# 16_RK3568_VI_Interface.net
KiCad netlist of a schematic drawn in Altium Designer
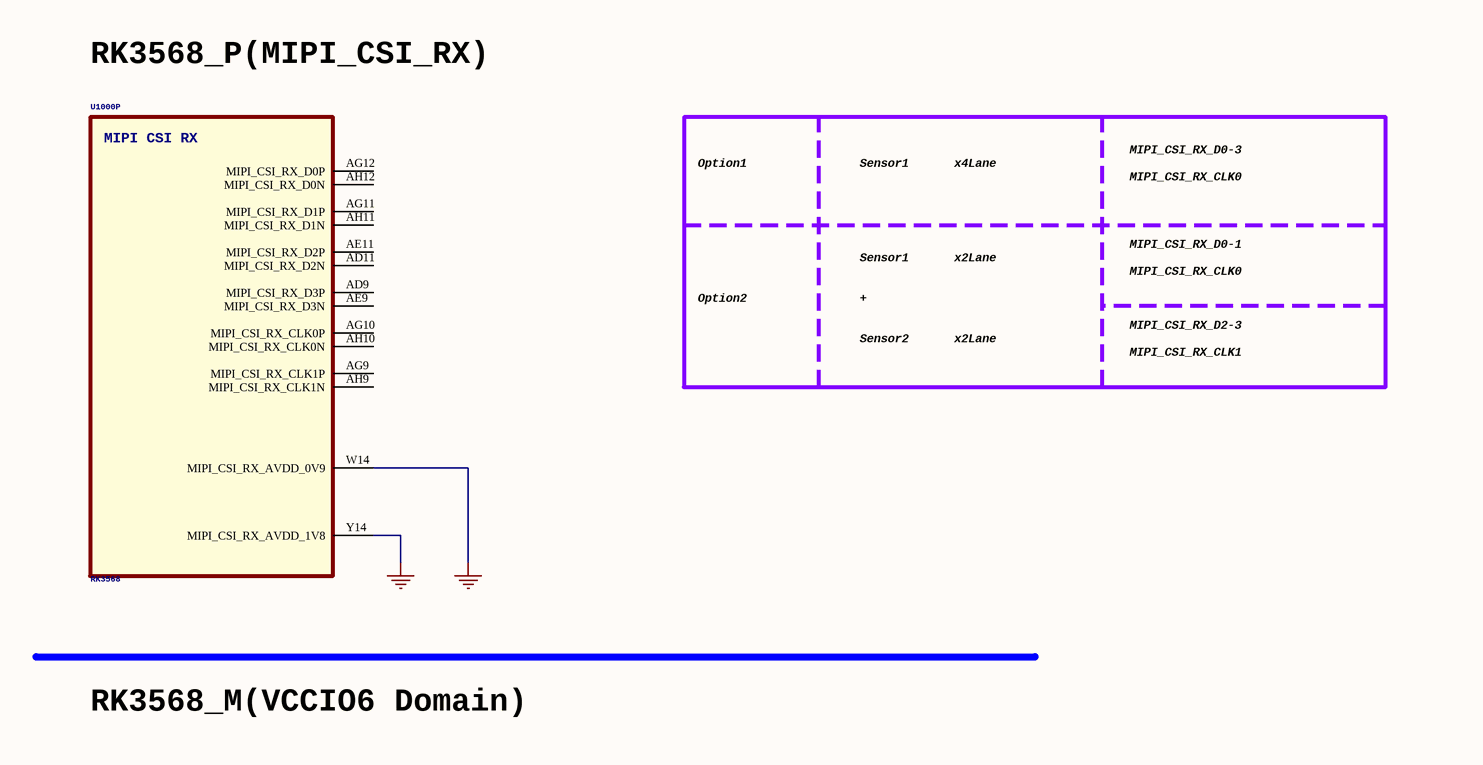
[diagram p0: 16.RK3568_VI Interface.SchDoc, top left]
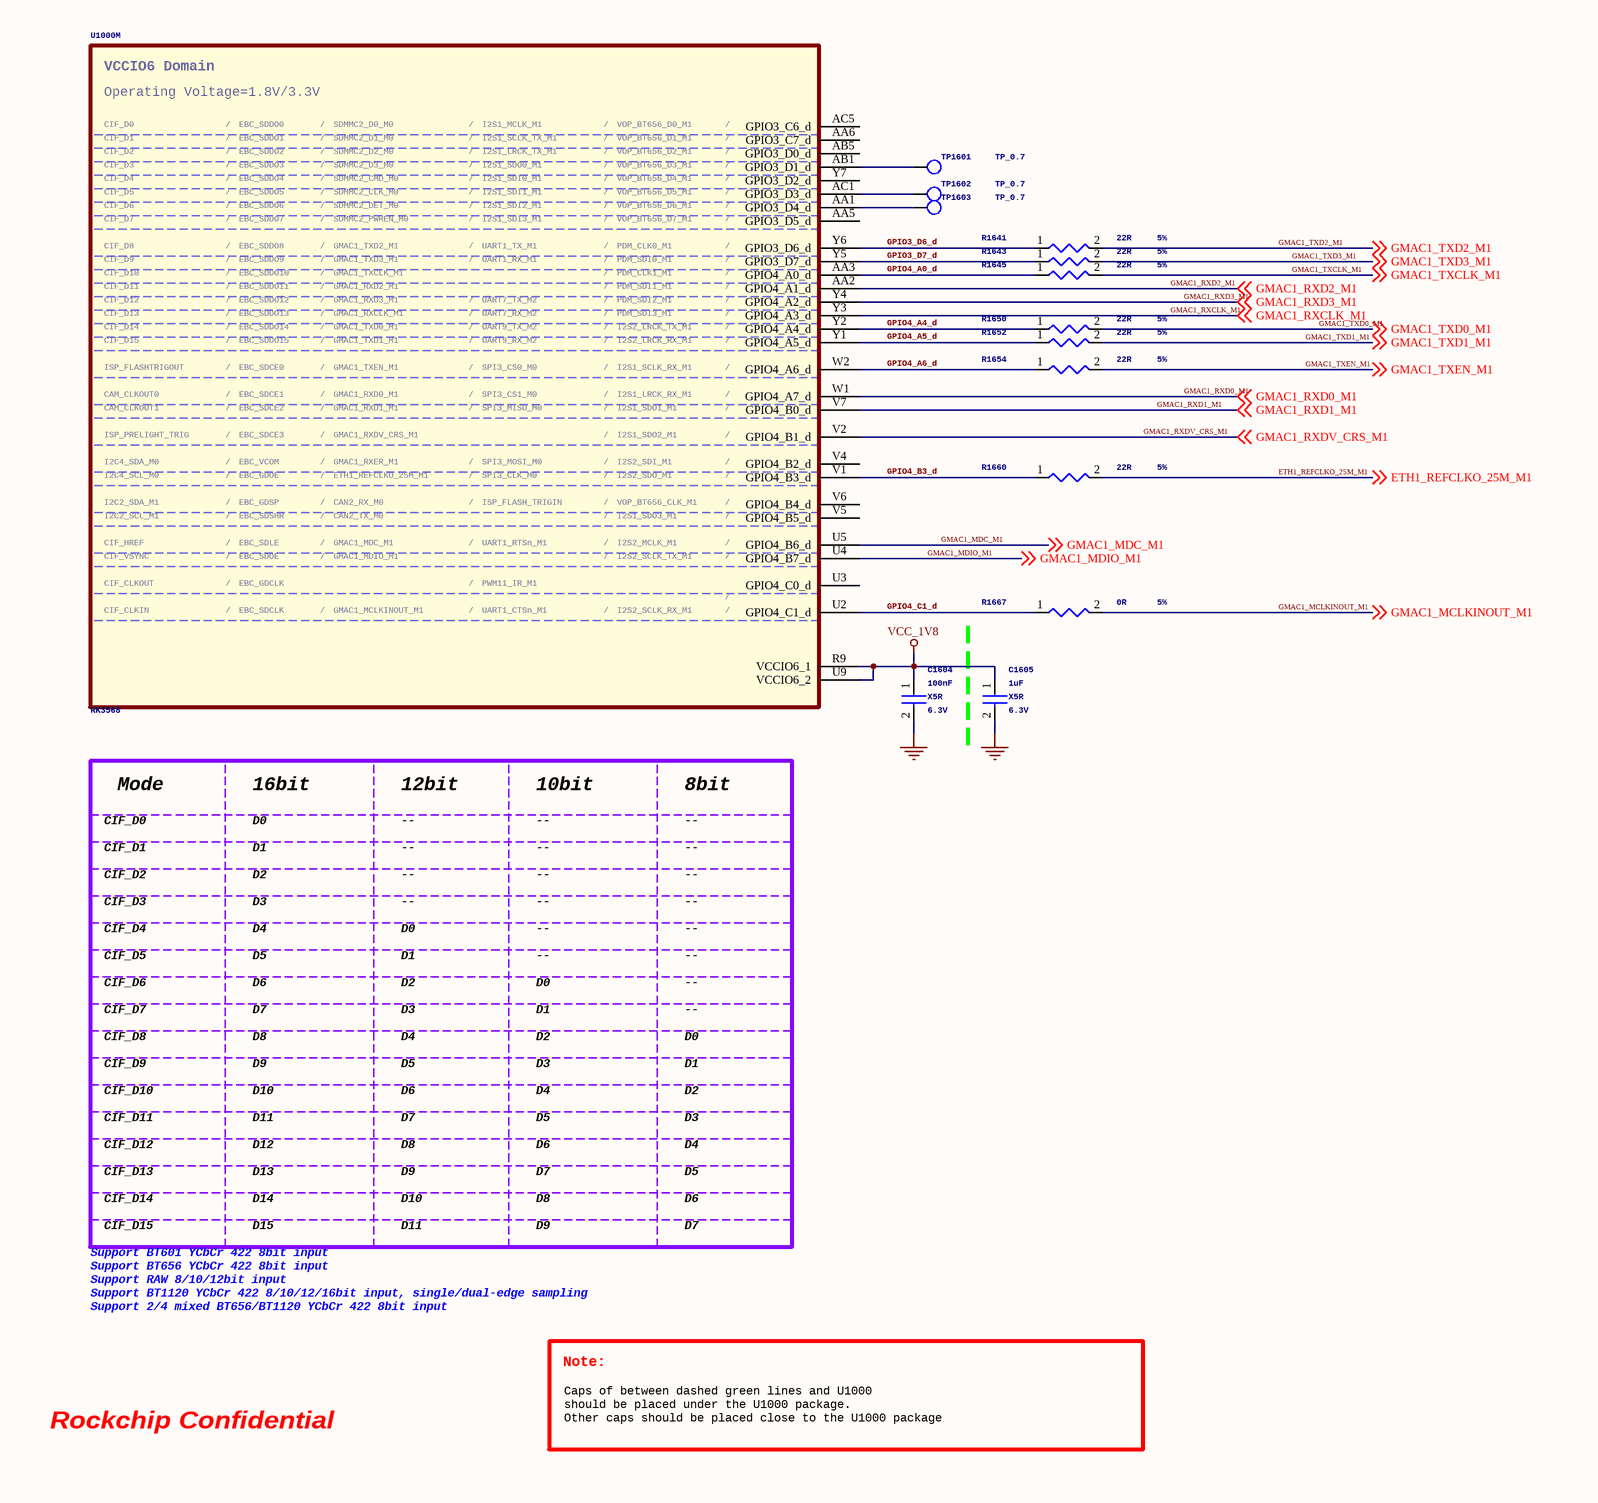
[diagram p1: 16.RK3568_VI Interface.SchDoc, bottom left]
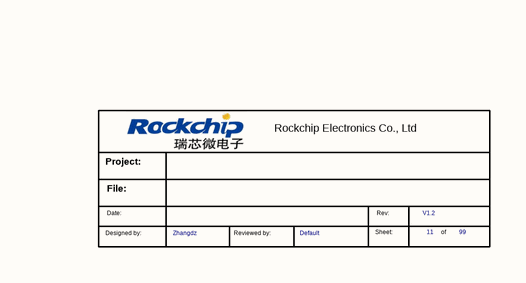
[diagram p2: 16.RK3568_VI Interface.SchDoc, bottom right]

(export (version "E")
  (design (tool "Eeschema 10.0.6"))
  (components
    (comp (ref "*")
      (value "Rockchip_new")
      (fields
        (field (name "SCHEMATIC PAGE COUNT") "99")
        (field (name "SCHEMATIC PAGE NUMBER") "11")
        (field (name "DESIGNER") "Zhangdz")
        (field (name "REVISION") "V1.2")
        (field (name "CHECK") "Default")
      )
      (libsource (lib "*") (part "Rockchip_new"))
    )
    (comp (ref "C1604")
      (value "100nF")
      (footprint "C0201")
      (description "cap,100.00nF,+/-10%,6.3V,X5R,C0201")
      (fields
        (field (name "VOLTAGE") "6.3V")
        (field (name "DIELECTRIC") "X5R")
        (field (name "TOLERANCE") "10%")
        (field (name "MANUFACTURER") "TDK")
        (field (name "CREATED BY") "JJJ")
      )
      (libsource (lib "*") (part "CAP NP"))
    )
    (comp (ref "C1605")
      (value "1uF")
      (footprint "C0402")
      (description "cap,1.00uF,+/-10%,6.3V,X5R,C0402")
      (fields
        (field (name "VOLTAGE") "6.3V")
        (field (name "DIELECTRIC") "X5R")
        (field (name "TOLERANCE") "10%")
        (field (name "MANUFACTURER") "TDK")
        (field (name "CREATED BY") "JJJ")
      )
      (libsource (lib "*") (part "CAP NP"))
    )
    (comp (ref "R1641")
      (value "22R")
      (footprint "R0402")
      (description "通用厚膜电阻,22R,+/-5%,R0402,1/16W.")
      (fields
        (field (name "TOLERANCE") "5%")
        (field (name "MANUFACTURER") "YAGEO")
        (field (name "CREATED BY") "YTL")
      )
      (libsource (lib "*") (part "RESISTOR"))
    )
    (comp (ref "R1643")
      (value "22R")
      (footprint "R0402")
      (description "通用厚膜电阻,22R,+/-5%,R0402,1/16W.")
      (fields
        (field (name "TOLERANCE") "5%")
        (field (name "MANUFACTURER") "YAGEO")
        (field (name "CREATED BY") "YTL")
      )
      (libsource (lib "*") (part "RESISTOR"))
    )
    (comp (ref "R1645")
      (value "22R")
      (footprint "R0402")
      (description "通用厚膜电阻,22R,+/-5%,R0402,1/16W.")
      (fields
        (field (name "TOLERANCE") "5%")
        (field (name "MANUFACTURER") "YAGEO")
        (field (name "CREATED BY") "YTL")
      )
      (libsource (lib "*") (part "RESISTOR"))
    )
    (comp (ref "R1650")
      (value "22R")
      (footprint "R0402")
      (description "通用厚膜电阻,22R,+/-5%,R0402,1/16W.")
      (fields
        (field (name "TOLERANCE") "5%")
        (field (name "MANUFACTURER") "YAGEO")
        (field (name "CREATED BY") "YTL")
      )
      (libsource (lib "*") (part "RESISTOR"))
    )
    (comp (ref "R1652")
      (value "22R")
      (footprint "R0402")
      (description "通用厚膜电阻,22R,+/-5%,R0402,1/16W.")
      (fields
        (field (name "TOLERANCE") "5%")
        (field (name "MANUFACTURER") "YAGEO")
        (field (name "CREATED BY") "YTL")
      )
      (libsource (lib "*") (part "RESISTOR"))
    )
    (comp (ref "R1654")
      (value "22R")
      (footprint "R0402")
      (description "通用厚膜电阻,22R,+/-5%,R0402,1/16W.")
      (fields
        (field (name "TOLERANCE") "5%")
        (field (name "MANUFACTURER") "YAGEO")
        (field (name "CREATED BY") "YTL")
      )
      (libsource (lib "*") (part "RESISTOR"))
    )
    (comp (ref "R1660")
      (value "22R")
      (footprint "R0402")
      (description "通用厚膜电阻,22R,+/-5%,R0402,1/16W.")
      (fields
        (field (name "TOLERANCE") "5%")
        (field (name "MANUFACTURER") "YAGEO")
        (field (name "CREATED BY") "YTL")
      )
      (libsource (lib "*") (part "RESISTOR"))
    )
    (comp (ref "R1667")
      (value "0R")
      (footprint "R0402")
      (description "通用厚膜电阻,0R,+/-5%,R0402,1/16W.")
      (fields
        (field (name "TOLERANCE") "5%")
        (field (name "MANUFACTURER") "YAGEO")
        (field (name "CREATED BY") "YTL")
      )
      (libsource (lib "*") (part "RESISTOR"))
    )
    (comp (ref "TP1601")
      (value "TP_0.7")
      (footprint "TP_0R70")
      (description "Test Point 0.7mm")
      (fields (field (name "CREATED BY") "JJJ"))
      (libsource (lib "*") (part "TP"))
    )
    (comp (ref "TP1602")
      (value "TP_0.7")
      (footprint "TP_0R70")
      (description "Test Point 0.7mm")
      (fields (field (name "CREATED BY") "JJJ"))
      (libsource (lib "*") (part "TP"))
    )
    (comp (ref "TP1603")
      (value "TP_0.7")
      (footprint "TP_0R70")
      (description "Test Point 0.7mm")
      (fields (field (name "CREATED BY") "JJJ"))
      (libsource (lib "*") (part "TP"))
    )
    (comp (ref "U1000")
      (value "RK3568")
      (footprint "BGA636_19R00X19R00X1R20")
      (description "ROCKCHIP SOC")
      (fields (field (name "MANUFACTURER") "Rockchip (瑞芯微)") (field (name "CREATED BY") "JJJ"))
      (libsource (lib "*") (part "SOC_RK3568"))
    )
  )
  (nets
    (net (code "1") (name "/GPIO3_D6_d") (class "Default")
      (node (ref "R1641") (pin "1") (pinfunction "1_1") (pintype "passive"))
      (node (ref "U1000") (pin "Y6") (pinfunction "GPIO3_D6_d_Y6") (pintype "passive"))
    )
    (net (code "2") (name "/GPIO3_D7_d") (class "Default")
      (node (ref "R1643") (pin "1") (pinfunction "1_1") (pintype "passive"))
      (node (ref "U1000") (pin "Y5") (pinfunction "GPIO3_D7_d_Y5") (pintype "passive"))
    )
    (net (code "3") (name "/GPIO4_A0_d") (class "Default")
      (node (ref "R1645") (pin "1") (pinfunction "1_1") (pintype "passive"))
      (node (ref "U1000") (pin "AA3") (pinfunction "GPIO4_A0_d_AA3") (pintype "passive"))
    )
    (net (code "4") (name "/GPIO4_A4_d") (class "Default")
      (node (ref "R1650") (pin "1") (pinfunction "1_1") (pintype "passive"))
      (node (ref "U1000") (pin "Y2") (pinfunction "GPIO4_A4_d_Y2") (pintype "passive"))
    )
    (net (code "5") (name "/GPIO4_A5_d") (class "Default")
      (node (ref "R1652") (pin "1") (pinfunction "1_1") (pintype "passive"))
      (node (ref "U1000") (pin "Y1") (pinfunction "GPIO4_A5_d_Y1") (pintype "passive"))
    )
    (net (code "6") (name "/GPIO4_A6_d") (class "Default")
      (node (ref "R1654") (pin "1") (pinfunction "1_1") (pintype "passive"))
      (node (ref "U1000") (pin "W2") (pinfunction "GPIO4_A6_d_W2") (pintype "passive"))
    )
    (net (code "7") (name "/GPIO4_B3_d") (class "Default")
      (node (ref "R1660") (pin "1") (pinfunction "1_1") (pintype "passive"))
      (node (ref "U1000") (pin "V1") (pinfunction "GPIO4_B3_d_V1") (pintype "passive"))
    )
    (net (code "8") (name "/GPIO4_C1_d") (class "Default")
      (node (ref "R1667") (pin "1") (pinfunction "1_1") (pintype "passive"))
      (node (ref "U1000") (pin "U2") (pinfunction "GPIO4_C1_d_U2") (pintype "passive"))
    )
    (net (code "9") (name "ETH1_REFCLKO_25M_M1") (class "Default")
      (node (ref "R1660") (pin "2") (pinfunction "2_2") (pintype "passive"))
    )
    (net (code "10") (name "GMAC1_MCLKINOUT_M1") (class "Default")
      (node (ref "R1667") (pin "2") (pinfunction "2_2") (pintype "passive"))
    )
    (net (code "11") (name "GMAC1_MDC_M1") (class "Default")
      (node (ref "U1000") (pin "U5") (pinfunction "GPIO4_B6_d_U5") (pintype "passive"))
    )
    (net (code "12") (name "GMAC1_MDIO_M1") (class "Default")
      (node (ref "U1000") (pin "U4") (pinfunction "GPIO4_B7_d_U4") (pintype "passive"))
    )
    (net (code "13") (name "GMAC1_RXCLK_M1") (class "Default")
      (node (ref "U1000") (pin "Y3") (pinfunction "GPIO4_A3_d_Y3") (pintype "passive"))
    )
    (net (code "14") (name "GMAC1_RXD0_M1") (class "Default")
      (node (ref "U1000") (pin "W1") (pinfunction "GPIO4_A7_d_W1") (pintype "passive"))
    )
    (net (code "15") (name "GMAC1_RXD1_M1") (class "Default")
      (node (ref "U1000") (pin "V7") (pinfunction "GPIO4_B0_d_V7") (pintype "passive"))
    )
    (net (code "16") (name "GMAC1_RXD2_M1") (class "Default")
      (node (ref "U1000") (pin "AA2") (pinfunction "GPIO4_A1_d_AA2") (pintype "passive"))
    )
    (net (code "17") (name "GMAC1_RXD3_M1") (class "Default")
      (node (ref "U1000") (pin "Y4") (pinfunction "GPIO4_A2_d_Y4") (pintype "passive"))
    )
    (net (code "18") (name "GMAC1_RXDV_CRS_M1") (class "Default")
      (node (ref "U1000") (pin "V2") (pinfunction "GPIO4_B1_d_V2") (pintype "passive"))
    )
    (net (code "19") (name "GMAC1_TXCLK_M1") (class "Default")
      (node (ref "R1645") (pin "2") (pinfunction "2_2") (pintype "passive"))
    )
    (net (code "20") (name "GMAC1_TXD0_M1") (class "Default")
      (node (ref "R1650") (pin "2") (pinfunction "2_2") (pintype "passive"))
    )
    (net (code "21") (name "GMAC1_TXD1_M1") (class "Default")
      (node (ref "R1652") (pin "2") (pinfunction "2_2") (pintype "passive"))
    )
    (net (code "22") (name "GMAC1_TXD2_M1") (class "Default")
      (node (ref "R1641") (pin "2") (pinfunction "2_2") (pintype "passive"))
    )
    (net (code "23") (name "GMAC1_TXD3_M1") (class "Default")
      (node (ref "R1643") (pin "2") (pinfunction "2_2") (pintype "passive"))
    )
    (net (code "24") (name "GMAC1_TXEN_M1") (class "Default")
      (node (ref "R1654") (pin "2") (pinfunction "2_2") (pintype "passive"))
    )
    (net (code "25") (name "GND") (class "Default")
      (node (ref "C1604") (pin "2") (pinfunction "2_2") (pintype "passive"))
      (node (ref "C1605") (pin "2") (pinfunction "2_2") (pintype "passive"))
      (node (ref "U1000") (pin "W14") (pinfunction "MIPI_CSI_RX_AVDD_0V9_W14") (pintype "passive"))
      (node (ref "U1000") (pin "Y14") (pinfunction "MIPI_CSI_RX_AVDD_1V8_Y14") (pintype "passive"))
    )
    (net (code "26") (name "Net-(U1000M-GPIO3_D1_d)") (class "Default")
      (node (ref "TP1601") (pin "1") (pinfunction "1_1") (pintype "passive"))
      (node (ref "U1000") (pin "AB1") (pinfunction "GPIO3_D1_d_AB1") (pintype "passive"))
    )
    (net (code "27") (name "Net-(U1000M-GPIO3_D3_d)") (class "Default")
      (node (ref "TP1602") (pin "1") (pinfunction "1_1") (pintype "passive"))
      (node (ref "U1000") (pin "AC1") (pinfunction "GPIO3_D3_d_AC1") (pintype "passive"))
    )
    (net (code "28") (name "Net-(U1000M-GPIO3_D4_d)") (class "Default")
      (node (ref "TP1603") (pin "1") (pinfunction "1_1") (pintype "passive"))
      (node (ref "U1000") (pin "AA1") (pinfunction "GPIO3_D4_d_AA1") (pintype "passive"))
    )
    (net (code "29") (name "VCC_1V8") (class "Default")
      (node (ref "C1604") (pin "1") (pinfunction "1_1") (pintype "passive"))
      (node (ref "C1605") (pin "1") (pinfunction "1_1") (pintype "passive"))
      (node (ref "U1000") (pin "R9") (pinfunction "VCCIO6_1_R9") (pintype "passive"))
      (node (ref "U1000") (pin "U9") (pinfunction "VCCIO6_2_U9") (pintype "passive"))
    )
    (net (code "30") (name "unconnected-(U1000M-GPIO3_C6_d-PadAC5)") (class "Default")
      (node (ref "U1000") (pin "AC5") (pinfunction "GPIO3_C6_d_AC5") (pintype "passive"))
    )
    (net (code "31") (name "unconnected-(U1000M-GPIO3_C7_d-PadAA6)") (class "Default")
      (node (ref "U1000") (pin "AA6") (pinfunction "GPIO3_C7_d_AA6") (pintype "passive"))
    )
    (net (code "32") (name "unconnected-(U1000M-GPIO3_D0_d-PadAB5)") (class "Default")
      (node (ref "U1000") (pin "AB5") (pinfunction "GPIO3_D0_d_AB5") (pintype "passive"))
    )
    (net (code "33") (name "unconnected-(U1000M-GPIO3_D2_d-PadY7)") (class "Default")
      (node (ref "U1000") (pin "Y7") (pinfunction "GPIO3_D2_d_Y7") (pintype "passive"))
    )
    (net (code "34") (name "unconnected-(U1000M-GPIO3_D5_d-PadAA5)") (class "Default")
      (node (ref "U1000") (pin "AA5") (pinfunction "GPIO3_D5_d_AA5") (pintype "passive"))
    )
    (net (code "35") (name "unconnected-(U1000M-GPIO4_B2_d-PadV4)") (class "Default")
      (node (ref "U1000") (pin "V4") (pinfunction "GPIO4_B2_d_V4") (pintype "passive"))
    )
    (net (code "36") (name "unconnected-(U1000M-GPIO4_B4_d-PadV6)") (class "Default")
      (node (ref "U1000") (pin "V6") (pinfunction "GPIO4_B4_d_V6") (pintype "passive"))
    )
    (net (code "37") (name "unconnected-(U1000M-GPIO4_B5_d-PadV5)") (class "Default")
      (node (ref "U1000") (pin "V5") (pinfunction "GPIO4_B5_d_V5") (pintype "passive"))
    )
    (net (code "38") (name "unconnected-(U1000M-GPIO4_C0_d-PadU3)") (class "Default")
      (node (ref "U1000") (pin "U3") (pinfunction "GPIO4_C0_d_U3") (pintype "passive"))
    )
    (net (code "39") (name "unconnected-(U1000P-MIPI_CSI_RX_CLK0N-PadAH10)") (class "Default")
      (node (ref "U1000") (pin "AH10") (pinfunction "MIPI_CSI_RX_CLK0N_AH10") (pintype "passive"))
    )
    (net (code "40") (name "unconnected-(U1000P-MIPI_CSI_RX_CLK0P-PadAG10)") (class "Default")
      (node (ref "U1000") (pin "AG10") (pinfunction "MIPI_CSI_RX_CLK0P_AG10") (pintype "passive"))
    )
    (net (code "41") (name "unconnected-(U1000P-MIPI_CSI_RX_CLK1N-PadAH9)") (class "Default")
      (node (ref "U1000") (pin "AH9") (pinfunction "MIPI_CSI_RX_CLK1N_AH9") (pintype "passive"))
    )
    (net (code "42") (name "unconnected-(U1000P-MIPI_CSI_RX_CLK1P-PadAG9)") (class "Default")
      (node (ref "U1000") (pin "AG9") (pinfunction "MIPI_CSI_RX_CLK1P_AG9") (pintype "passive"))
    )
    (net (code "43") (name "unconnected-(U1000P-MIPI_CSI_RX_D0N-PadAH12)") (class "Default")
      (node (ref "U1000") (pin "AH12") (pinfunction "MIPI_CSI_RX_D0N_AH12") (pintype "passive"))
    )
    (net (code "44") (name "unconnected-(U1000P-MIPI_CSI_RX_D0P-PadAG12)") (class "Default")
      (node (ref "U1000") (pin "AG12") (pinfunction "MIPI_CSI_RX_D0P_AG12") (pintype "passive"))
    )
    (net (code "45") (name "unconnected-(U1000P-MIPI_CSI_RX_D1N-PadAH11)") (class "Default")
      (node (ref "U1000") (pin "AH11") (pinfunction "MIPI_CSI_RX_D1N_AH11") (pintype "passive"))
    )
    (net (code "46") (name "unconnected-(U1000P-MIPI_CSI_RX_D1P-PadAG11)") (class "Default")
      (node (ref "U1000") (pin "AG11") (pinfunction "MIPI_CSI_RX_D1P_AG11") (pintype "passive"))
    )
    (net (code "47") (name "unconnected-(U1000P-MIPI_CSI_RX_D2N-PadAD11)") (class "Default")
      (node (ref "U1000") (pin "AD11") (pinfunction "MIPI_CSI_RX_D2N_AD11") (pintype "passive"))
    )
    (net (code "48") (name "unconnected-(U1000P-MIPI_CSI_RX_D2P-PadAE11)") (class "Default")
      (node (ref "U1000") (pin "AE11") (pinfunction "MIPI_CSI_RX_D2P_AE11") (pintype "passive"))
    )
    (net (code "49") (name "unconnected-(U1000P-MIPI_CSI_RX_D3N-PadAE9)") (class "Default")
      (node (ref "U1000") (pin "AE9") (pinfunction "MIPI_CSI_RX_D3N_AE9") (pintype "passive"))
    )
    (net (code "50") (name "unconnected-(U1000P-MIPI_CSI_RX_D3P-PadAD9)") (class "Default")
      (node (ref "U1000") (pin "AD9") (pinfunction "MIPI_CSI_RX_D3P_AD9") (pintype "passive"))
    )
  )
)
